# Main.net
KiCad netlist of a schematic drawn in Altium Designer
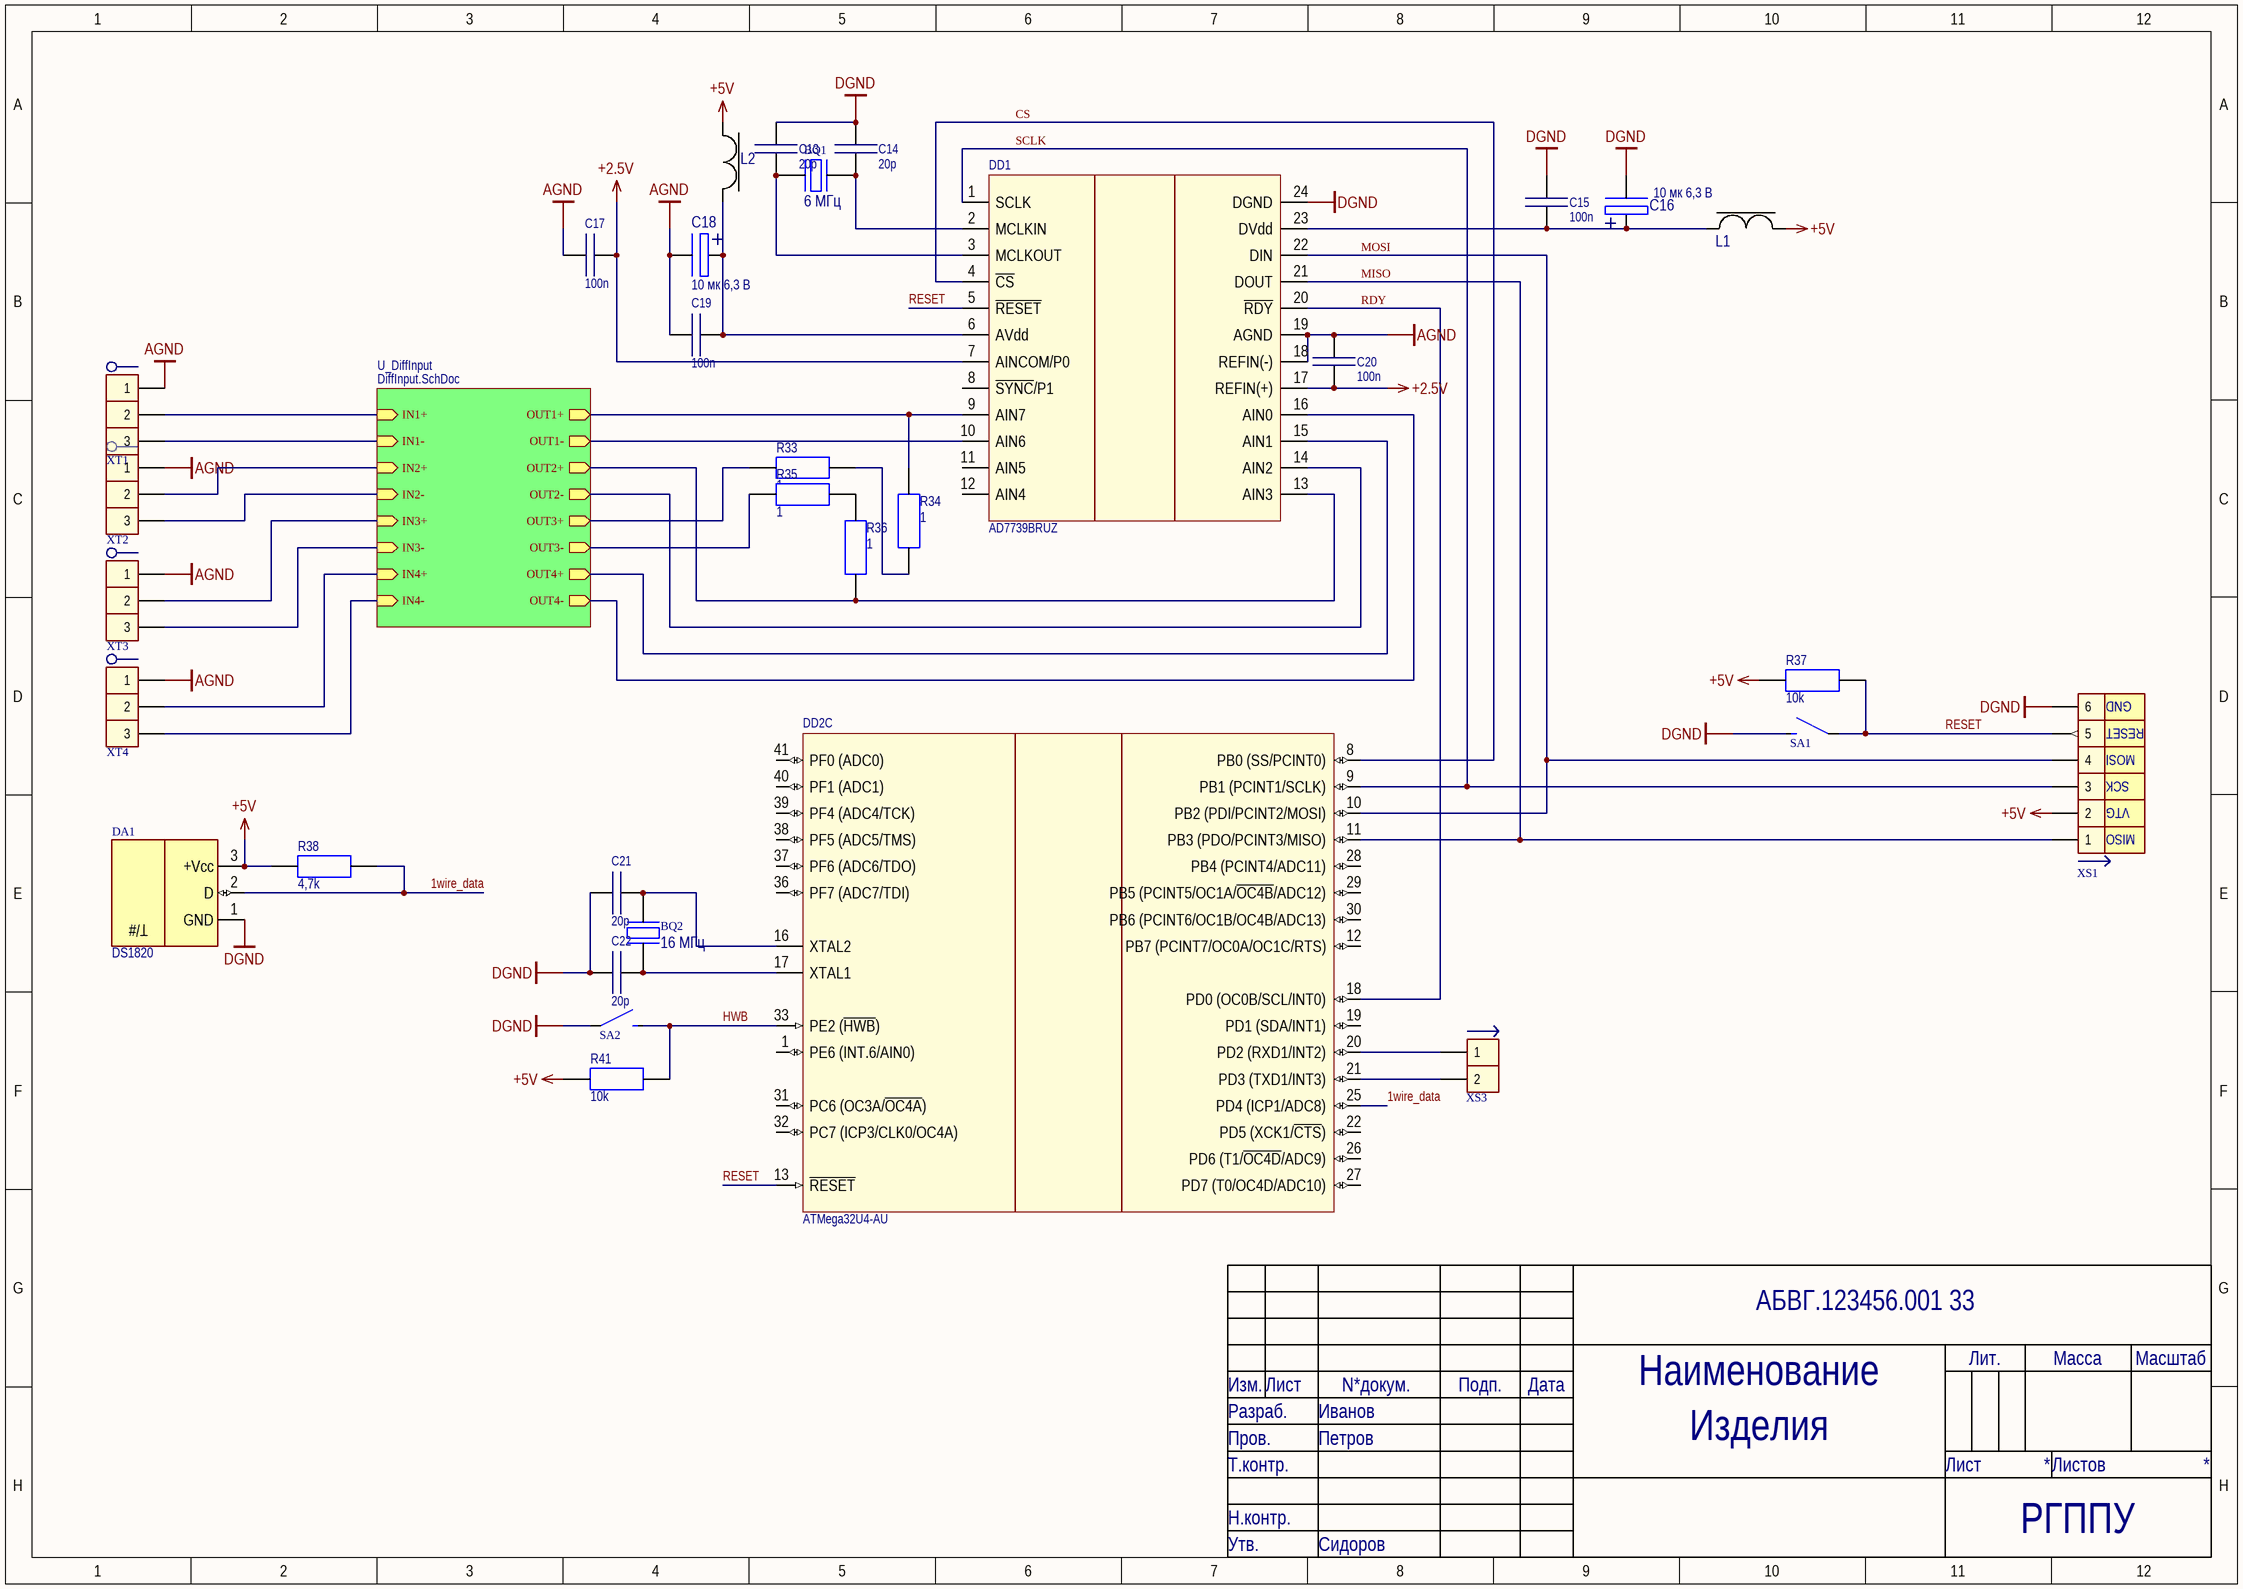
[diagram p0: Main.SchDoc]

(export (version "E")
  (design (tool "Eeschema 10.0.6"))
  (components
    (comp (ref "BQ1")
      (value "6 МГц")
      (footprint "Piezoelectric:HC-49/S")
      (description "Piezoelectric elements")
      (fields (field (name "MANUFACTURER") "Taizhou") (field (name "MANUFACTURERPARTNUMBER") "6000 кГц"))
      (libsource (lib "Piezoelectric") (part "Piezoelectric_6000"))
    )
    (comp (ref "BQ2")
      (value "16 МГц")
      (footprint "Piezoelectric:HC-49/S")
      (description "Piezoelectric elements")
      (fields
        (field (name "MANUFACTURER") "Taizhou")
        (field (name "MANUFACTURERPARTNUMBER") "16000 кГц 20ppm 20pF")
      )
      (libsource (lib "Piezoelectric") (part "Piezoelectric_16000"))
    )
    (comp (ref "C13")
      (value "20p")
      (footprint "SMDRC0805")
      (description "Generic capasitor non-polar")
      (fields (field (name "PARTNUMBER") "Capacitor 0805 20p"))
      (libsource (lib "library") (part "Capacitor"))
    )
    (comp (ref "C14")
      (value "20p")
      (footprint "SMDRC0805")
      (description "Generic capasitor non-polar")
      (fields (field (name "PARTNUMBER") "Capacitor 0805 20p"))
      (libsource (lib "library") (part "Capacitor"))
    )
    (comp (ref "C15")
      (value "100n")
      (footprint "SMDRC0805")
      (description "Generic capasitor non-polar")
      (fields (field (name "PARTNUMBER") "Capacitor 0805 100n"))
      (libsource (lib "library") (part "Capacitor"))
    )
    (comp (ref "C16")
      (value "10 мк 6,3 В")
      (footprint "К50-6")
      (description "10uF 6,3V Polar through-hole cap")
      (fields (field (name "MANUFACTURERPARTNUMBER") "К-50-6"))
      (libsource (lib "Cap") (part "10000_006-К50"))
    )
    (comp (ref "C17")
      (value "100n")
      (footprint "SMDRC0805")
      (description "Generic capasitor non-polar")
      (fields (field (name "PARTNUMBER") "Capacitor 0805 100n"))
      (libsource (lib "library") (part "Capacitor"))
    )
    (comp (ref "C18")
      (value "10 мк 6,3 В")
      (footprint "К50-6")
      (description "10uF 6,3V Polar through-hole cap")
      (fields (field (name "MANUFACTURERPARTNUMBER") "К-50-6"))
      (libsource (lib "Cap") (part "10000_006-К50"))
    )
    (comp (ref "C19")
      (value "100n")
      (footprint "SMDRC0805")
      (description "Generic capasitor non-polar")
      (fields (field (name "PARTNUMBER") "Capacitor 0805 100n"))
      (libsource (lib "library") (part "Capacitor"))
    )
    (comp (ref "C20")
      (value "100n")
      (footprint "SMDRC0805")
      (description "Generic capasitor non-polar")
      (fields (field (name "PARTNUMBER") "Capacitor 0805 100n"))
      (libsource (lib "library") (part "Capacitor"))
    )
    (comp (ref "C21")
      (value "20p")
      (footprint "SMDRC0805")
      (description "Generic capasitor non-polar")
      (fields (field (name "PARTNUMBER") "Capacitor 0805 20p"))
      (libsource (lib "library") (part "Capacitor"))
    )
    (comp (ref "C22")
      (value "20p")
      (footprint "SMDRC0805")
      (description "Generic capasitor non-polar")
      (fields (field (name "PARTNUMBER") "Capacitor 0805 20p"))
      (libsource (lib "library") (part "Capacitor"))
    )
    (comp (ref "DA1")
      (value "DS1820")
      (footprint "Power:L78L09")
      (description "Precision Micropower Shunt Voltage Reference")
      (fields
        (field (name "MANUFACTURER") "Dallas Semiconductor")
        (field (name "MANUFACTURERPARTNUMBER") "DS1820")
      )
      (libsource (lib "Sensor") (part "T_DS1820"))
    )
    (comp (ref "DD1")
      (value "AD7739BRUZ")
      (footprint "Standard:TSSOP-RU-24")
      (description "IC ADC 24BIT 8-CH 24-TSSOP")
      (fields (field (name "MANUFACTURER") "Analog Devices Inc."))
      (libsource (lib "Interface") (part "AD7739"))
    )
    (comp (ref "DD2")
      (value "ATMega32U4-AU")
      (footprint "Atmel Microcontroller 8-Bit Automotive AVR:44ML_L")
      (libsource (lib "Microcontrollers") (part "ATMega32U4"))
    )
    (comp (ref "L1")
      (value "MPZ1608S181A")
      (footprint "Inductor:INDC0603X03M")
      (description "Ferrite Bead")
      (libsource (lib "Inductor") (part "Ferrite Bead"))
    )
    (comp (ref "L2")
      (value "MPZ1608S181A")
      (footprint "Inductor:INDC0603X03M")
      (description "Ferrite Bead")
      (libsource (lib "") (part "Ferrite Bead_1"))
    )
    (comp (ref "R33")
      (value "1")
      (footprint "SMDRC0805")
      (description "Generic resistor")
      (fields (field (name "PARTNUMBER") "Resistor 0805 1"))
      (libsource (lib "") (part "Resistor_1"))
    )
    (comp (ref "R34")
      (value "1")
      (footprint "SMDRC0805")
      (description "Generic resistor")
      (fields (field (name "PARTNUMBER") "Resistor 0805 1"))
      (libsource (lib "library") (part "Resistor"))
    )
    (comp (ref "R35")
      (value "1")
      (footprint "SMDRC0805")
      (description "Generic resistor")
      (fields (field (name "PARTNUMBER") "Resistor 0805 1"))
      (libsource (lib "") (part "Resistor_1"))
    )
    (comp (ref "R36")
      (value "1")
      (footprint "SMDRC0805")
      (description "Generic resistor")
      (fields (field (name "PARTNUMBER") "Resistor 0805 1"))
      (libsource (lib "library") (part "Resistor"))
    )
    (comp (ref "R37")
      (value "10k")
      (footprint "SMDRC0805")
      (description "Generic resistor")
      (fields (field (name "PARTNUMBER") "Resistor 0805 10k"))
      (libsource (lib "") (part "Resistor_2"))
    )
    (comp (ref "R38")
      (value "4,7k")
      (footprint "SMDRC0805")
      (description "Generic resistor")
      (fields (field (name "PARTNUMBER") "Resistor 0805 4,7k"))
      (libsource (lib "") (part "Resistor_2"))
    )
    (comp (ref "R41")
      (value "10k")
      (footprint "SMDRC0805")
      (description "Generic resistor")
      (fields (field (name "PARTNUMBER") "Resistor 0805 10k"))
      (libsource (lib "") (part "Resistor_2"))
    )
    (comp (ref "SA1")
      (value "DTSM20-4.3")
      (footprint "Switch:DTSM20")
      (description "Switch open")
      (fields (field (name "MANUFACTURER") "Diptronics"))
      (libsource (lib "Switch") (part "Switch1_DTSM20-4.3"))
    )
    (comp (ref "SA2")
      (value "DTSM20-4.3")
      (footprint "Switch:DTSM20")
      (description "Switch open")
      (fields (field (name "MANUFACTURER") "Diptronics"))
      (libsource (lib "Switch") (part "Switch1_DTSM20-4.3"))
    )
    (comp (ref "XS1")
      (value "IDC-06M")
      (footprint "Connector:IDC-06M")
      (description "SPI connector")
      (libsource (lib "Connector") (part "Con6_M IDC-06M_SPI"))
    )
    (comp (ref "XS3")
      (value "PLS-02")
      (footprint "Connector:PLS-02")
      (description "Male 2-pin connection")
      (libsource (lib "Connector") (part "Con2_M_PLS-02"))
    )
    (comp (ref "XT1")
      (value "330-031-12")
      (footprint "Connector:330-031-12")
      (description "Demountable connection 3-pin")
      (fields (field (name "MANUFACTURER") "Degson Electronics Co., Ltd"))
      (libsource (lib "Connector") (part "Con3_D 330-031-12"))
    )
    (comp (ref "XT2")
      (value "330-031-12")
      (footprint "Connector:330-031-12")
      (description "Demountable connection 3-pin")
      (fields (field (name "MANUFACTURER") "Degson Electronics Co., Ltd"))
      (libsource (lib "Connector") (part "Con3_D 330-031-12"))
    )
    (comp (ref "XT3")
      (value "330-031-12")
      (footprint "Connector:330-031-12")
      (description "Demountable connection 3-pin")
      (fields (field (name "MANUFACTURER") "Degson Electronics Co., Ltd"))
      (libsource (lib "Connector") (part "Con3_D 330-031-12"))
    )
    (comp (ref "XT4")
      (value "330-031-12")
      (footprint "Connector:330-031-12")
      (description "Demountable connection 3-pin")
      (fields (field (name "MANUFACTURER") "Degson Electronics Co., Ltd"))
      (libsource (lib "Connector") (part "Con3_D 330-031-12"))
    )
  )
  (nets
    (net (code "1") (name "+2.5V") (class "Default")
      (node (ref "C17") (pin "2") (pintype "passive"))
      (node (ref "C20") (pin "1") (pintype "passive"))
      (node (ref "DD1") (pin "17") (pinfunction "REFIN(+)_17") (pintype "passive"))
      (node (ref "DD1") (pin "7") (pinfunction "AINCOM/P0_7") (pintype "passive"))
    )
    (net (code "2") (name "+5V") (class "Default")
      (node (ref "DA1") (pin "3") (pinfunction "+Vcc_3") (pintype "power_in"))
      (node (ref "L1") (pin "2") (pinfunction "2_2") (pintype "passive"))
      (node (ref "L2") (pin "1") (pinfunction "1_1") (pintype "passive"))
      (node (ref "R37") (pin "2") (pinfunction "2_2") (pintype "passive"))
      (node (ref "R38") (pin "2") (pinfunction "2_2") (pintype "passive"))
      (node (ref "R41") (pin "2") (pinfunction "2_2") (pintype "passive"))
      (node (ref "XS1") (pin "2") (pinfunction "2_2") (pintype "passive"))
    )
    (net (code "3") (name "/1wire_data") (class "Default")
      (node (ref "DA1") (pin "2") (pinfunction "D_2") (pintype "bidirectional"))
      (node (ref "DD2") (pin "25") (pinfunction "PD4_(ICP1/ADC8)_25") (pintype "bidirectional"))
      (node (ref "R38") (pin "1") (pinfunction "1_1") (pintype "passive"))
    )
    (net (code "4") (name "/CS") (class "Default")
      (node (ref "DD1") (pin "4") (pinfunction "~{CS}_4") (pintype "passive"))
      (node (ref "DD2") (pin "8") (pinfunction "PB0_(SS/PCINT0)_8") (pintype "bidirectional"))
    )
    (net (code "5") (name "/HWB") (class "Default")
      (node (ref "DD2") (pin "33") (pinfunction "PE2_(~{HWB})_33") (pintype "input"))
      (node (ref "R41") (pin "1") (pinfunction "1_1") (pintype "passive"))
      (node (ref "SA2") (pin "2") (pinfunction "2_2") (pintype "output"))
    )
    (net (code "6") (name "/IN1+") (class "Default")
      (node (ref "XT1") (pin "2") (pinfunction "2_2") (pintype "passive"))
    )
    (net (code "7") (name "/IN1-") (class "Default")
      (node (ref "XT1") (pin "3") (pinfunction "3_3") (pintype "passive"))
    )
    (net (code "8") (name "/IN2+") (class "Default")
      (node (ref "XT2") (pin "2") (pinfunction "2_2") (pintype "passive"))
    )
    (net (code "9") (name "/IN2-") (class "Default")
      (node (ref "XT2") (pin "3") (pinfunction "3_3") (pintype "passive"))
    )
    (net (code "10") (name "/IN3+") (class "Default")
      (node (ref "XT3") (pin "2") (pinfunction "2_2") (pintype "passive"))
    )
    (net (code "11") (name "/IN3-") (class "Default")
      (node (ref "XT3") (pin "3") (pinfunction "3_3") (pintype "passive"))
    )
    (net (code "12") (name "/IN4+") (class "Default")
      (node (ref "XT4") (pin "2") (pinfunction "2_2") (pintype "passive"))
    )
    (net (code "13") (name "/IN4-") (class "Default")
      (node (ref "XT4") (pin "3") (pinfunction "3_3") (pintype "passive"))
    )
    (net (code "14") (name "/MISO") (class "Default")
      (node (ref "DD1") (pin "21") (pinfunction "DOUT_21") (pintype "passive"))
      (node (ref "DD2") (pin "11") (pinfunction "PB3_(PDO/PCINT3/MISO)_11") (pintype "bidirectional"))
      (node (ref "XS1") (pin "1") (pinfunction "1_1") (pintype "passive"))
    )
    (net (code "15") (name "/MOSI") (class "Default")
      (node (ref "DD1") (pin "22") (pinfunction "DIN_22") (pintype "passive"))
      (node (ref "DD2") (pin "10") (pinfunction "PB2_(PDI/PCINT2/MOSI)_10") (pintype "bidirectional"))
      (node (ref "XS1") (pin "4") (pinfunction "4_4") (pintype "passive"))
    )
    (net (code "16") (name "/OUT1+") (class "Default")
      (node (ref "DD1") (pin "9") (pinfunction "AIN7_9") (pintype "passive"))
      (node (ref "R34") (pin "2") (pinfunction "2_2") (pintype "passive"))
    )
    (net (code "17") (name "/OUT1-") (class "Default")
      (node (ref "DD1") (pin "10") (pinfunction "AIN6_10") (pintype "passive"))
    )
    (net (code "18") (name "/OUT2+") (class "Default")
      (node (ref "DD1") (pin "13") (pinfunction "AIN3_13") (pintype "passive"))
      (node (ref "R36") (pin "1") (pinfunction "1_1") (pintype "passive"))
    )
    (net (code "19") (name "/OUT2-") (class "Default")
      (node (ref "DD1") (pin "14") (pinfunction "AIN2_14") (pintype "passive"))
    )
    (net (code "20") (name "/OUT3+") (class "Default")
      (node (ref "R33") (pin "1") (pinfunction "1_1") (pintype "passive"))
    )
    (net (code "21") (name "/OUT3-") (class "Default")
      (node (ref "R35") (pin "1") (pinfunction "1_1") (pintype "passive"))
    )
    (net (code "22") (name "/OUT4+") (class "Default")
      (node (ref "DD1") (pin "15") (pinfunction "AIN1_15") (pintype "passive"))
    )
    (net (code "23") (name "/OUT4-") (class "Default")
      (node (ref "DD1") (pin "16") (pinfunction "AIN0_16") (pintype "passive"))
    )
    (net (code "24") (name "/RDY") (class "Default")
      (node (ref "DD1") (pin "20") (pinfunction "~{RDY}_20") (pintype "passive"))
      (node (ref "DD2") (pin "18") (pinfunction "PD0_(OC0B/SCL/INT0)_18") (pintype "bidirectional"))
    )
    (net (code "25") (name "/RESET") (class "Default")
      (node (ref "DD1") (pin "5") (pinfunction "~{RESET}_5") (pintype "passive"))
      (node (ref "DD2") (pin "13") (pinfunction "~{RESET}_13") (pintype "input"))
      (node (ref "R37") (pin "1") (pinfunction "1_1") (pintype "passive"))
      (node (ref "SA1") (pin "1") (pinfunction "1_1") (pintype "passive"))
      (node (ref "XS1") (pin "5") (pinfunction "5_5") (pintype "output"))
    )
    (net (code "26") (name "/SCLK") (class "Default")
      (node (ref "DD1") (pin "1") (pinfunction "SCLK_1") (pintype "passive"))
      (node (ref "DD2") (pin "9") (pinfunction "PB1_(PCINT1/SCLK)_9") (pintype "bidirectional"))
      (node (ref "XS1") (pin "3") (pinfunction "3_3") (pintype "passive"))
    )
    (net (code "27") (name "AGND") (class "Default")
      (node (ref "C17") (pin "1") (pintype "passive"))
      (node (ref "C18") (pin "1") (pinfunction "-_1") (pintype "passive"))
      (node (ref "C19") (pin "2") (pintype "passive"))
      (node (ref "C20") (pin "2") (pintype "passive"))
      (node (ref "DD1") (pin "18") (pinfunction "REFIN(-)_18") (pintype "passive"))
      (node (ref "DD1") (pin "19") (pinfunction "AGND_19") (pintype "passive"))
      (node (ref "XT1") (pin "1") (pinfunction "1_1") (pintype "passive"))
      (node (ref "XT2") (pin "1") (pinfunction "1_1") (pintype "passive"))
      (node (ref "XT3") (pin "1") (pinfunction "1_1") (pintype "passive"))
      (node (ref "XT4") (pin "1") (pinfunction "1_1") (pintype "passive"))
    )
    (net (code "28") (name "DGND") (class "Default")
      (node (ref "C13") (pin "1") (pintype "passive"))
      (node (ref "C14") (pin "1") (pintype "passive"))
      (node (ref "C15") (pin "2") (pintype "passive"))
      (node (ref "C16") (pin "1") (pinfunction "-_1") (pintype "passive"))
      (node (ref "C21") (pin "1") (pintype "passive"))
      (node (ref "C22") (pin "1") (pintype "passive"))
      (node (ref "DA1") (pin "1") (pinfunction "GND_1") (pintype "power_in"))
      (node (ref "DD1") (pin "24") (pinfunction "DGND_24") (pintype "passive"))
      (node (ref "SA1") (pin "2") (pinfunction "2_2") (pintype "output"))
      (node (ref "SA2") (pin "1") (pinfunction "1_1") (pintype "passive"))
      (node (ref "XS1") (pin "6") (pinfunction "6_6") (pintype "passive"))
    )
    (net (code "29") (name "Net-(C16-+)") (class "Default")
      (node (ref "C15") (pin "1") (pintype "passive"))
      (node (ref "C16") (pin "2") (pinfunction "+_2") (pintype "passive"))
      (node (ref "DD1") (pin "23") (pinfunction "DVdd_23") (pintype "passive"))
      (node (ref "L1") (pin "1") (pinfunction "1_1") (pintype "passive"))
    )
    (net (code "30") (name "Net-(C18-+)") (class "Default")
      (node (ref "C18") (pin "2") (pinfunction "+_2") (pintype "passive"))
      (node (ref "C19") (pin "1") (pintype "passive"))
      (node (ref "DD1") (pin "6") (pinfunction "AVdd_6") (pintype "passive"))
      (node (ref "L2") (pin "2") (pinfunction "2_2") (pintype "passive"))
    )
    (net (code "31") (name "Net-(DD1-MCLKIN)") (class "Default")
      (node (ref "BQ1") (pin "2") (pinfunction "2_2") (pintype "passive"))
      (node (ref "C14") (pin "2") (pintype "passive"))
      (node (ref "DD1") (pin "2") (pinfunction "MCLKIN_2") (pintype "passive"))
    )
    (net (code "32") (name "Net-(DD1-MCLKOUT)") (class "Default")
      (node (ref "BQ1") (pin "1") (pinfunction "1_1") (pintype "passive"))
      (node (ref "C13") (pin "2") (pintype "passive"))
      (node (ref "DD1") (pin "3") (pinfunction "MCLKOUT_3") (pintype "passive"))
    )
    (net (code "33") (name "Net-(DD2C-PD2_(RXD1{slash}INT2))") (class "Default")
      (node (ref "DD2") (pin "20") (pinfunction "PD2_(RXD1/INT2)_20") (pintype "bidirectional"))
      (node (ref "XS3") (pin "1") (pinfunction "1_1") (pintype "passive"))
    )
    (net (code "34") (name "Net-(DD2C-PD3_(TXD1{slash}INT3))") (class "Default")
      (node (ref "DD2") (pin "21") (pinfunction "PD3_(TXD1/INT3)_21") (pintype "bidirectional"))
      (node (ref "XS3") (pin "2") (pinfunction "2_2") (pintype "passive"))
    )
    (net (code "35") (name "Net-(DD2C-XTAL1)") (class "Default")
      (node (ref "BQ2") (pin "1") (pinfunction "1_1") (pintype "passive"))
      (node (ref "C22") (pin "2") (pintype "passive"))
      (node (ref "DD2") (pin "17") (pinfunction "XTAL1_17") (pintype "passive"))
    )
    (net (code "36") (name "Net-(DD2C-XTAL2)") (class "Default")
      (node (ref "BQ2") (pin "2") (pinfunction "2_2") (pintype "passive"))
      (node (ref "C21") (pin "2") (pintype "passive"))
      (node (ref "DD2") (pin "16") (pinfunction "XTAL2_16") (pintype "passive"))
    )
    (net (code "37") (name "Net-(R33-Pad2)") (class "Default")
      (node (ref "R33") (pin "2") (pinfunction "2_2") (pintype "passive"))
      (node (ref "R34") (pin "1") (pinfunction "1_1") (pintype "passive"))
    )
    (net (code "38") (name "Net-(R35-Pad2)") (class "Default")
      (node (ref "R35") (pin "2") (pinfunction "2_2") (pintype "passive"))
      (node (ref "R36") (pin "2") (pinfunction "2_2") (pintype "passive"))
    )
    (net (code "39") (name "unconnected-(DD1-AIN4-Pad12)") (class "Default")
      (node (ref "DD1") (pin "12") (pinfunction "AIN4_12") (pintype "passive"))
    )
    (net (code "40") (name "unconnected-(DD1-AIN5-Pad11)") (class "Default")
      (node (ref "DD1") (pin "11") (pinfunction "AIN5_11") (pintype "passive"))
    )
    (net (code "41") (name "unconnected-(DD1-~{SYNC}{slash}P1-Pad8)") (class "Default")
      (node (ref "DD1") (pin "8") (pinfunction "~{SYNC}/P1_8") (pintype "passive"))
    )
    (net (code "42") (name "unconnected-(DD2C-PB4_(PCINT4{slash}ADC11)-Pad28)") (class "Default")
      (node (ref "DD2") (pin "28") (pinfunction "PB4_(PCINT4/ADC11)_28") (pintype "bidirectional"))
    )
    (net (code "43") (name "unconnected-(DD2C-PB5_(PCINT5{slash}OC1A{slash}~{OC4B}{slash}ADC12)-Pad29)") (class "Default")
      (node (ref "DD2") (pin "29") (pinfunction "PB5_(PCINT5/OC1A/~{OC4B}/ADC12)_29") (pintype "bidirectional"))
    )
    (net (code "44") (name "unconnected-(DD2C-PB6_(PCINT6{slash}OC1B{slash}OC4B{slash}ADC13)-Pad30)") (class "Default")
      (node (ref "DD2") (pin "30") (pinfunction "PB6_(PCINT6/OC1B/OC4B/ADC13)_30") (pintype "bidirectional"))
    )
    (net (code "45") (name "unconnected-(DD2C-PB7_(PCINT7{slash}OC0A{slash}OC1C{slash}RTS)-Pad12)") (class "Default")
      (node (ref "DD2") (pin "12") (pinfunction "PB7_(PCINT7/OC0A/OC1C/RTS)_12") (pintype "bidirectional"))
    )
    (net (code "46") (name "unconnected-(DD2C-PC6_(OC3A{slash}~{OC4A})-Pad31)") (class "Default")
      (node (ref "DD2") (pin "31") (pinfunction "PC6_(OC3A/~{OC4A})_31") (pintype "bidirectional"))
    )
    (net (code "47") (name "unconnected-(DD2C-PC7_(ICP3{slash}CLK0{slash}OC4A)-Pad32)") (class "Default")
      (node (ref "DD2") (pin "32") (pinfunction "PC7_(ICP3/CLK0/OC4A)_32") (pintype "bidirectional"))
    )
    (net (code "48") (name "unconnected-(DD2C-PD1_(SDA{slash}INT1)-Pad19)") (class "Default")
      (node (ref "DD2") (pin "19") (pinfunction "PD1_(SDA/INT1)_19") (pintype "bidirectional"))
    )
    (net (code "49") (name "unconnected-(DD2C-PD5_(XCK1{slash}~{CTS})-Pad22)") (class "Default")
      (node (ref "DD2") (pin "22") (pinfunction "PD5_(XCK1/~{CTS})_22") (pintype "bidirectional"))
    )
    (net (code "50") (name "unconnected-(DD2C-PD6_(T1{slash}~{OC4D}{slash}ADC9)-Pad26)") (class "Default")
      (node (ref "DD2") (pin "26") (pinfunction "PD6_(T1/~{OC4D}/ADC9)_26") (pintype "bidirectional"))
    )
    (net (code "51") (name "unconnected-(DD2C-PD7_(T0{slash}OC4D{slash}ADC10)-Pad27)") (class "Default")
      (node (ref "DD2") (pin "27") (pinfunction "PD7_(T0/OC4D/ADC10)_27") (pintype "bidirectional"))
    )
    (net (code "52") (name "unconnected-(DD2C-PE6_(INT.6{slash}AIN0)-Pad1)") (class "Default")
      (node (ref "DD2") (pin "1") (pinfunction "PE6_(INT.6/AIN0)_1") (pintype "bidirectional"))
    )
    (net (code "53") (name "unconnected-(DD2C-PF0_(ADC0)-Pad41)") (class "Default")
      (node (ref "DD2") (pin "41") (pinfunction "PF0_(ADC0)_41") (pintype "bidirectional"))
    )
    (net (code "54") (name "unconnected-(DD2C-PF1_(ADC1)-Pad40)") (class "Default")
      (node (ref "DD2") (pin "40") (pinfunction "PF1_(ADC1)_40") (pintype "bidirectional"))
    )
    (net (code "55") (name "unconnected-(DD2C-PF4_(ADC4{slash}TCK)-Pad39)") (class "Default")
      (node (ref "DD2") (pin "39") (pinfunction "PF4_(ADC4/TCK)_39") (pintype "bidirectional"))
    )
    (net (code "56") (name "unconnected-(DD2C-PF5_(ADC5{slash}TMS)-Pad38)") (class "Default")
      (node (ref "DD2") (pin "38") (pinfunction "PF5_(ADC5/TMS)_38") (pintype "bidirectional"))
    )
    (net (code "57") (name "unconnected-(DD2C-PF6_(ADC6{slash}TDO)-Pad37)") (class "Default")
      (node (ref "DD2") (pin "37") (pinfunction "PF6_(ADC6/TDO)_37") (pintype "bidirectional"))
    )
    (net (code "58") (name "unconnected-(DD2C-PF7_(ADC7{slash}TDI)-Pad36)") (class "Default")
      (node (ref "DD2") (pin "36") (pinfunction "PF7_(ADC7/TDI)_36") (pintype "bidirectional"))
    )
  )
)
